# FREA-K.net
KiCad netlist of a schematic drawn in EAGLE
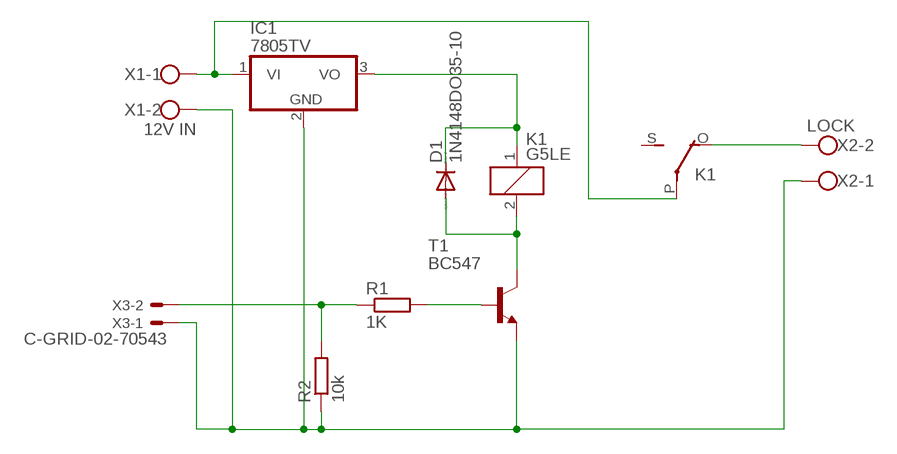
[diagram p0: schematic, sheet 1]

(export (version "E")
  (design (tool "Eeschema 10.0.6"))
  (components
    (comp (ref "D1")
      (value "1N4148DO35-10")
      (footprint "eagle-import:DO35-10")
      (libsource (lib "eagle-import") (part "1N4148DO35-10"))
    )
    (comp (ref "IC1")
      (value "7805TV")
      (footprint "eagle-import:TO220V")
      (libsource (lib "eagle-import") (part "78TV05"))
    )
    (comp (ref "K1")
      (value "G5LE")
      (footprint "eagle-import:G5LE")
      (libsource (lib "eagle-import") (part "G5LE"))
    )
    (comp (ref "R1")
      (value "1K")
      (footprint "eagle-import:0204_7")
      (libsource (lib "eagle-import") (part "R-EU_0204/7"))
    )
    (comp (ref "R2")
      (value "10k")
      (footprint "eagle-import:0204_7")
      (libsource (lib "eagle-import") (part "R-EU_0204/7"))
    )
    (comp (ref "T1")
      (value "BC547")
      (footprint "eagle-import:TO92")
      (libsource (lib "eagle-import") (part "BC547"))
    )
    (comp (ref "X1")
      (value "12V IN")
      (footprint "eagle-import:W237-102")
      (fields (field (name "MPN") "237-102"))
      (libsource (lib "eagle-import") (part "W237-102"))
    )
    (comp (ref "X2")
      (value "LOCK")
      (footprint "eagle-import:W237-102")
      (fields (field (name "MPN") "237-102"))
      (libsource (lib "eagle-import") (part "W237-102"))
    )
    (comp (ref "X3")
      (value "C-GRID-02-70543")
      (footprint "eagle-import:70543-02")
      (libsource (lib "eagle-import") (part "C-GRID-02-70543"))
    )
  )
  (nets
    (net (code "1") (name "Net-(IC1-GND)") (class "Default")
      (node (ref "IC1") (pin "2") (pinfunction "GND_2") (pintype "passive"))
      (node (ref "R2") (pin "1") (pinfunction "1_1") (pintype "passive"))
      (node (ref "T1") (pin "1") (pinfunction "E_1") (pintype "passive"))
      (node (ref "X1") (pin "2") (pinfunction "KL_2") (pintype "passive"))
      (node (ref "X2") (pin "1") (pinfunction "KL_1") (pintype "passive"))
      (node (ref "X3") (pin "1") (pinfunction "S_1") (pintype "passive"))
    )
    (net (code "2") (name "Net-(IC1-VI)") (class "Default")
      (node (ref "IC1") (pin "1") (pinfunction "VI_1") (pintype "input"))
      (node (ref "K1") (pin "P") (pinfunction "P_P") (pintype "passive"))
      (node (ref "X1") (pin "1") (pinfunction "KL_1") (pintype "passive"))
    )
    (net (code "3") (name "Net-(IC1-VO)") (class "Default")
      (node (ref "D1") (pin "C") (pinfunction "C_C") (pintype "passive"))
      (node (ref "IC1") (pin "3") (pinfunction "VO_3") (pintype "passive"))
      (node (ref "K1") (pin "1") (pinfunction "1_1") (pintype "passive"))
    )
    (net (code "4") (name "Net-(T1-B)") (class "Default")
      (node (ref "R1") (pin "2") (pinfunction "2_2") (pintype "passive"))
      (node (ref "T1") (pin "2") (pinfunction "B_2") (pintype "passive"))
    )
    (net (code "5") (name "Net-(T1-C)") (class "Default")
      (node (ref "D1") (pin "A") (pinfunction "A_A") (pintype "passive"))
      (node (ref "K1") (pin "2") (pinfunction "2_2") (pintype "passive"))
      (node (ref "T1") (pin "3") (pinfunction "C_3") (pintype "passive"))
    )
    (net (code "6") (name "Net-(X2B-KL)") (class "Default")
      (node (ref "K1") (pin "O") (pinfunction "O_O") (pintype "passive"))
      (node (ref "X2") (pin "2") (pinfunction "KL_2") (pintype "passive"))
    )
    (net (code "7") (name "Net-(X3B-S)") (class "Default")
      (node (ref "R1") (pin "1") (pinfunction "1_1") (pintype "passive"))
      (node (ref "R2") (pin "2") (pinfunction "2_2") (pintype "passive"))
      (node (ref "X3") (pin "2") (pinfunction "S_2") (pintype "passive"))
    )
    (net (code "8") (name "unconnected-(K1-PadS)") (class "Default")
      (node (ref "K1") (pin "S") (pinfunction "S_S") (pintype "passive"))
    )
  )
)
